# compute_module_HDMI_out.net
KiCad netlist of a schematic drawn in Altium Designer
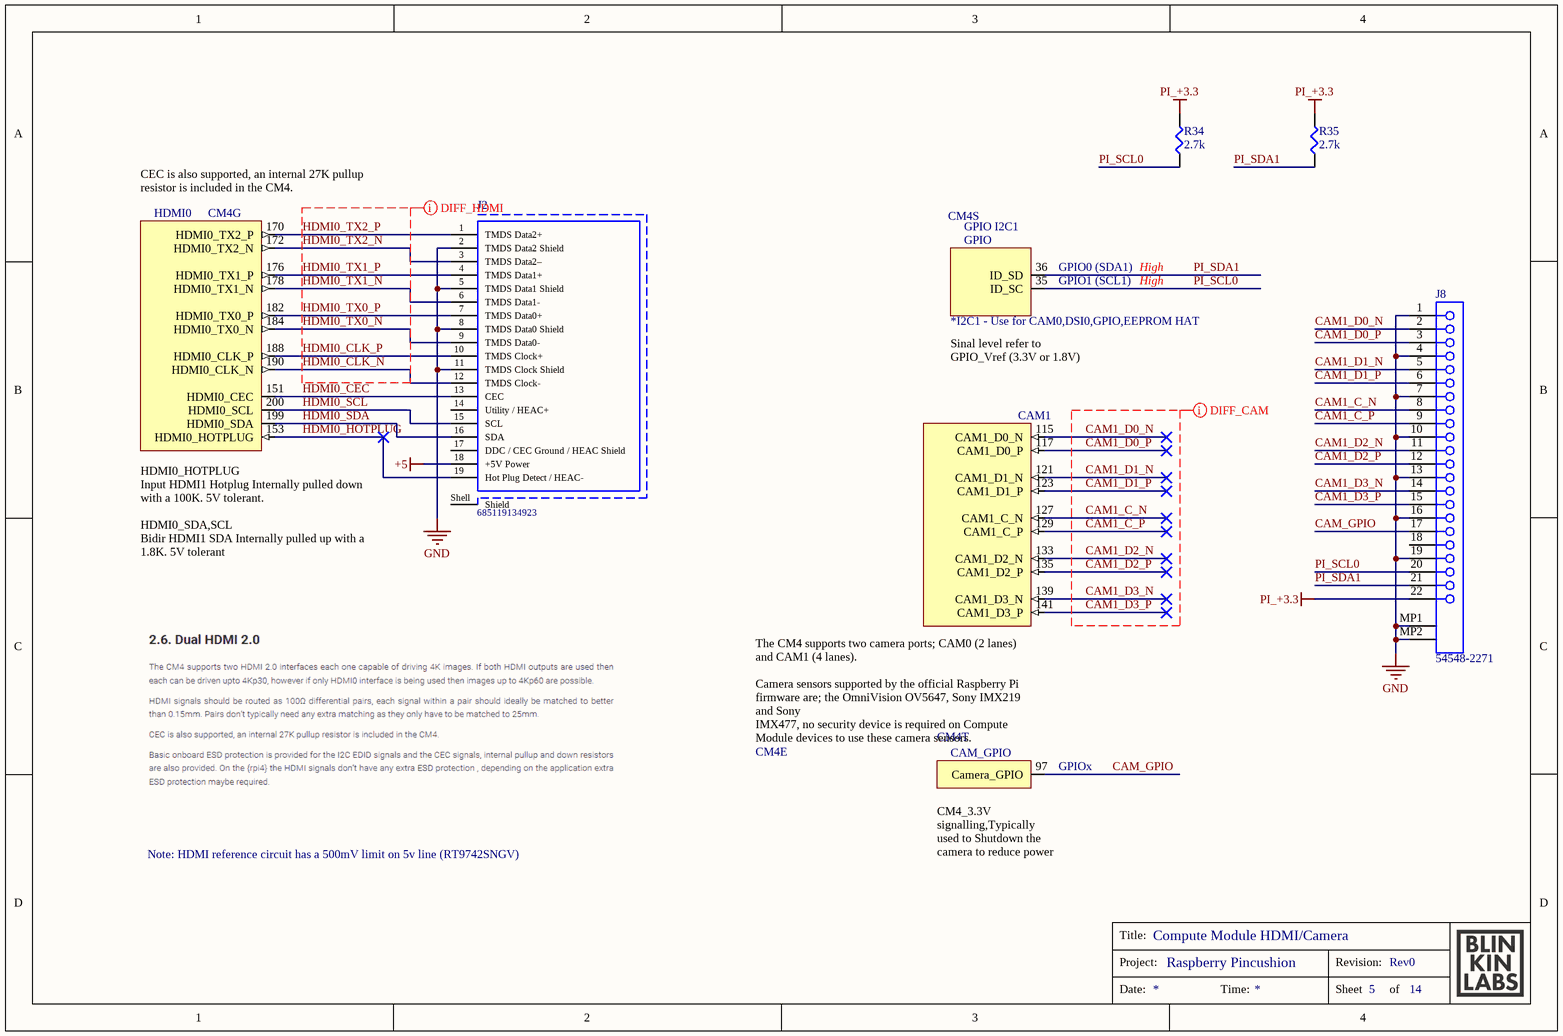
[diagram p0: compute module HDMI out.SchDoc]

(export (version "E")
  (design (tool "Eeschema 10.0.6"))
  (components
    (comp (ref "CM4")
      (value "Raspberry Pi Compute Module 4")
      (footprint "CM4-F40C-100DS-0.4v_1.5mm_0mm")
      (description "Raspberry Pi Compute Module 4 by Amornthep Phunsin")
      (libsource (lib "") (part "CM4_1"))
    )
    (comp (ref "J2")
      (value "685119134923")
      (footprint "685119134923")
      (description "HDMI Type A Receptacle WR-HDMI, Horizontal, SMT")
      (fields (field (name "MANUFACTURER") "Wurth Elektronik") (field (name "PUBLISHER") "WurthElektronik"))
      (libsource (lib "Altium Content Vault") (part "WE-CN-1P-1F-HD19"))
    )
    (comp (ref "J8")
      (value "54548-2271")
      (footprint "MOLX-54548-2271")
      (fields (field (name "MANUFACTURER") "Molex"))
      (libsource (lib "Altium Content Vault") (part "MOLX-54548-2271"))
    )
    (comp (ref "R34")
      (value "2.7k")
      (footprint "ERJ2G(0402)_L")
      (description "RES SMD 2.7K OHM 1% 1/10W 0402")
      (fields
        (field (name "PARTNUMBER") "ERJ-2RKF2701X")
        (field (name "DIGI-KEY PART NUMBER") "P2.70KLCT-ND")
      )
      (libsource (lib "res_panasonic_erj_xls") (part "RESISTOR"))
    )
    (comp (ref "R35")
      (value "2.7k")
      (footprint "ERJ2G(0402)_L")
      (description "RES SMD 2.7K OHM 1% 1/10W 0402")
      (fields
        (field (name "PARTNUMBER") "ERJ-2RKF2701X")
        (field (name "DIGI-KEY PART NUMBER") "P2.70KLCT-ND")
      )
      (libsource (lib "res_panasonic_erj_xls") (part "RESISTOR"))
    )
  )
  (nets
    (net (code "1") (name "+5") (class "Default")
      (node (ref "J2") (pin "18") (pinfunction "+5V_Power_18") (pintype "passive"))
    )
    (net (code "2") (name "/CAM1_C_N") (class "Default")
      (node (ref "CM4") (pin "127") (pinfunction "CAM1_C_N_127") (pintype "input"))
      (node (ref "J8") (pin "8") (pinfunction "8_8") (pintype "passive"))
    )
    (net (code "3") (name "/CAM1_C_P") (class "Default")
      (node (ref "CM4") (pin "129") (pinfunction "CAM1_C_P_129") (pintype "input"))
      (node (ref "J8") (pin "9") (pinfunction "9_9") (pintype "passive"))
    )
    (net (code "4") (name "/CAM1_D0_N") (class "Default")
      (node (ref "CM4") (pin "115") (pinfunction "CAM1_D0_N_115") (pintype "input"))
      (node (ref "J8") (pin "2") (pinfunction "2_2") (pintype "passive"))
    )
    (net (code "5") (name "/CAM1_D0_P") (class "Default")
      (node (ref "CM4") (pin "117") (pinfunction "CAM1_D0_P_117") (pintype "input"))
      (node (ref "J8") (pin "3") (pinfunction "3_3") (pintype "passive"))
    )
    (net (code "6") (name "/CAM1_D1_N") (class "Default")
      (node (ref "CM4") (pin "121") (pinfunction "CAM1_D1_N_121") (pintype "input"))
      (node (ref "J8") (pin "5") (pinfunction "5_5") (pintype "passive"))
    )
    (net (code "7") (name "/CAM1_D1_P") (class "Default")
      (node (ref "CM4") (pin "123") (pinfunction "CAM1_D1_P_123") (pintype "input"))
      (node (ref "J8") (pin "6") (pinfunction "6_6") (pintype "passive"))
    )
    (net (code "8") (name "/CAM1_D2_N") (class "Default")
      (node (ref "CM4") (pin "133") (pinfunction "CAM1_D2_N_133") (pintype "input"))
      (node (ref "J8") (pin "11") (pinfunction "11_11") (pintype "passive"))
    )
    (net (code "9") (name "/CAM1_D2_P") (class "Default")
      (node (ref "CM4") (pin "135") (pinfunction "CAM1_D2_P_135") (pintype "input"))
      (node (ref "J8") (pin "12") (pinfunction "12_12") (pintype "passive"))
    )
    (net (code "10") (name "/CAM1_D3_N") (class "Default")
      (node (ref "CM4") (pin "139") (pinfunction "CAM1_D3_N_139") (pintype "input"))
      (node (ref "J8") (pin "14") (pinfunction "14_14") (pintype "passive"))
    )
    (net (code "11") (name "/CAM1_D3_P") (class "Default")
      (node (ref "CM4") (pin "141") (pinfunction "CAM1_D3_P_141") (pintype "input"))
      (node (ref "J8") (pin "15") (pinfunction "15_15") (pintype "passive"))
    )
    (net (code "12") (name "/CAM_GPIO") (class "Default")
      (node (ref "CM4") (pin "97") (pinfunction "Camera_GPIO_97") (pintype "passive"))
      (node (ref "J8") (pin "17") (pinfunction "17_17") (pintype "passive"))
    )
    (net (code "13") (name "/HDMI0_CEC") (class "Default")
      (node (ref "CM4") (pin "151") (pinfunction "HDMI0_CEC_151") (pintype "open_collector"))
      (node (ref "J2") (pin "13") (pinfunction "CEC_13") (pintype "passive"))
    )
    (net (code "14") (name "/HDMI0_CLK_N") (class "Default")
      (node (ref "CM4") (pin "190") (pinfunction "HDMI0_CLK_N_190") (pintype "output"))
      (node (ref "J2") (pin "12") (pinfunction "TMDS_Clock-_12") (pintype "passive"))
    )
    (net (code "15") (name "/HDMI0_CLK_P") (class "Default")
      (node (ref "CM4") (pin "188") (pinfunction "HDMI0_CLK_P_188") (pintype "output"))
      (node (ref "J2") (pin "10") (pinfunction "TMDS_Clock+_10") (pintype "passive"))
    )
    (net (code "16") (name "/HDMI0_HOTPLUG") (class "Default")
      (node (ref "CM4") (pin "153") (pinfunction "HDMI0_HOTPLUG_153") (pintype "input"))
      (node (ref "J2") (pin "19") (pinfunction "Hot_Plug_Detect_/_HEAC-_19") (pintype "passive"))
    )
    (net (code "17") (name "/HDMI0_SCL") (class "Default")
      (node (ref "CM4") (pin "200") (pinfunction "HDMI0_SCL_200") (pintype "open_collector"))
      (node (ref "J2") (pin "15") (pinfunction "SCL_15") (pintype "passive"))
    )
    (net (code "18") (name "/HDMI0_SDA") (class "Default")
      (node (ref "CM4") (pin "199") (pinfunction "HDMI0_SDA_199") (pintype "bidirectional"))
      (node (ref "J2") (pin "16") (pinfunction "SDA_16") (pintype "passive"))
    )
    (net (code "19") (name "/HDMI0_TX0_N") (class "Default")
      (node (ref "CM4") (pin "184") (pinfunction "HDMI0_TX0_N_184") (pintype "output"))
      (node (ref "J2") (pin "9") (pinfunction "TMDS_Data0-_9") (pintype "passive"))
    )
    (net (code "20") (name "/HDMI0_TX0_P") (class "Default")
      (node (ref "CM4") (pin "182") (pinfunction "HDMI0_TX0_P_182") (pintype "output"))
      (node (ref "J2") (pin "7") (pinfunction "TMDS_Data0+_7") (pintype "passive"))
    )
    (net (code "21") (name "/HDMI0_TX1_N") (class "Default")
      (node (ref "CM4") (pin "178") (pinfunction "HDMI0_TX1_N_178") (pintype "output"))
      (node (ref "J2") (pin "6") (pinfunction "TMDS_Data1-_6") (pintype "passive"))
    )
    (net (code "22") (name "/HDMI0_TX1_P") (class "Default")
      (node (ref "CM4") (pin "176") (pinfunction "HDMI0_TX1_P_176") (pintype "output"))
      (node (ref "J2") (pin "4") (pinfunction "TMDS_Data1+_4") (pintype "passive"))
    )
    (net (code "23") (name "/HDMI0_TX2_N") (class "Default")
      (node (ref "CM4") (pin "172") (pinfunction "HDMI0_TX2_N_172") (pintype "output"))
      (node (ref "J2") (pin "3") (pinfunction "TMDS_Data2–_3") (pintype "passive"))
    )
    (net (code "24") (name "/HDMI0_TX2_P") (class "Default")
      (node (ref "CM4") (pin "170") (pinfunction "HDMI0_TX2_P_170") (pintype "output"))
      (node (ref "J2") (pin "1") (pinfunction "TMDS_Data2+_1") (pintype "passive"))
    )
    (net (code "25") (name "/PI_SCL0") (class "Default")
      (node (ref "CM4") (pin "35") (pinfunction "ID_SC_35") (pintype "passive"))
      (node (ref "J8") (pin "20") (pinfunction "20_20") (pintype "passive"))
      (node (ref "R34") (pin "1") (pinfunction "1_1") (pintype "passive"))
    )
    (net (code "26") (name "/PI_SDA1") (class "Default")
      (node (ref "CM4") (pin "36") (pinfunction "ID_SD_36") (pintype "passive"))
      (node (ref "J8") (pin "21") (pinfunction "21_21") (pintype "passive"))
      (node (ref "R35") (pin "1") (pinfunction "1_1") (pintype "passive"))
    )
    (net (code "27") (name "GND") (class "Default")
      (node (ref "J2") (pin "11") (pinfunction "TMDS_Clock_Shield_11") (pintype "passive"))
      (node (ref "J2") (pin "2") (pinfunction "TMDS_Data2_Shield_2") (pintype "passive"))
      (node (ref "J2") (pin "5") (pinfunction "TMDS_Data1_Shield_5") (pintype "passive"))
      (node (ref "J2") (pin "8") (pinfunction "TMDS_Data0_Shield_8") (pintype "passive"))
      (node (ref "J8") (pin "1") (pinfunction "1_1") (pintype "passive"))
      (node (ref "J8") (pin "10") (pinfunction "10_10") (pintype "passive"))
      (node (ref "J8") (pin "13") (pinfunction "13_13") (pintype "passive"))
      (node (ref "J8") (pin "16") (pinfunction "16_16") (pintype "passive"))
      (node (ref "J8") (pin "19") (pinfunction "19_19") (pintype "passive"))
      (node (ref "J8") (pin "4") (pinfunction "4_4") (pintype "passive"))
      (node (ref "J8") (pin "7") (pinfunction "7_7") (pintype "passive"))
      (node (ref "J8") (pin "MP1") (pinfunction "MP1_MP1") (pintype "passive"))
      (node (ref "J8") (pin "MP2") (pinfunction "MP2_MP2") (pintype "passive"))
    )
    (net (code "28") (name "PI_+3.3") (class "Default")
      (node (ref "J8") (pin "22") (pinfunction "22_22") (pintype "passive"))
      (node (ref "R34") (pin "2") (pinfunction "2_2") (pintype "passive"))
      (node (ref "R35") (pin "2") (pinfunction "2_2") (pintype "passive"))
    )
    (net (code "29") (name "unconnected-(J2-DDC_{slash}_CEC_Ground_{slash}_HEAC_Shield-Pad17)") (class "Default")
      (node (ref "J2") (pin "17") (pinfunction "DDC_/_CEC_Ground_/_HEAC_Shield_17") (pintype "passive"))
    )
    (net (code "30") (name "unconnected-(J2-Shield-PadShell)") (class "Default")
      (node (ref "J2") (pin "Shell") (pinfunction "Shield_Shell") (pintype "passive"))
    )
    (net (code "31") (name "unconnected-(J2-Utility_{slash}_HEAC+-Pad14)") (class "Default")
      (node (ref "J2") (pin "14") (pinfunction "Utility_/_HEAC+_14") (pintype "passive"))
    )
    (net (code "32") (name "unconnected-(J8-Pad18)") (class "Default")
      (node (ref "J8") (pin "18") (pinfunction "18_18") (pintype "passive"))
    )
  )
)
